# Schema.net
KiCad netlist of a schematic drawn in Altium Designer
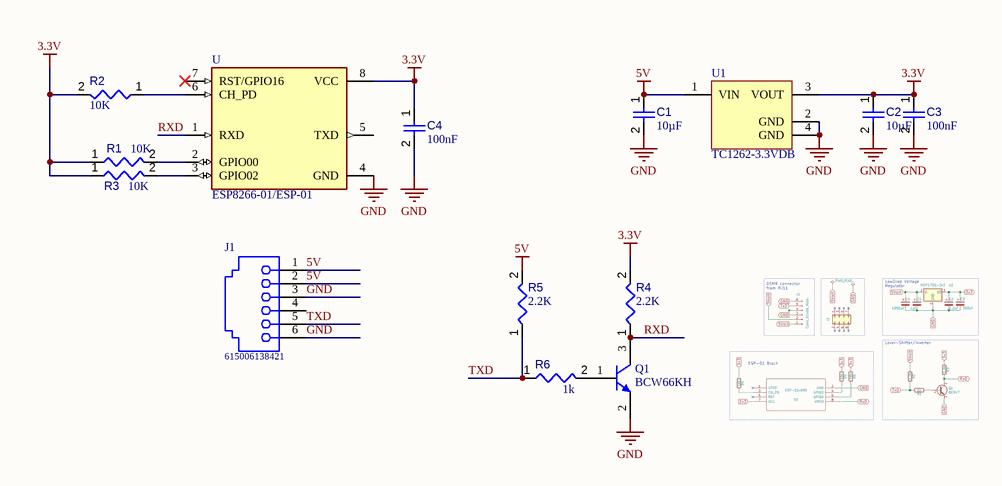
[diagram p0: Schema.SchDoc]

(export (version "E")
  (design (tool "Eeschema 10.0.6"))
  (components
    (comp (ref "C1")
      (value "10µF")
      (footprint "CAPC0805(2012)145_L")
      (description "Chip Capacitor, 10µF +/-20%, 25V, 0805, Thickness 1.45 mm")
      (fields (field (name "TOLERANCE") "10%") (field (name "Comment") "Capacitor 10µF +/-20% 25V 0805"))
      (libsource (lib "Merced College") (part "CAP-NP-2"))
    )
    (comp (ref "C2")
      (value "10µF")
      (footprint "CAPC0805(2012)145_L")
      (description "Chip Capacitor, 10µF +/-20%, 25V, 0805, Thickness 1.45 mm")
      (fields (field (name "TOLERANCE") "10%") (field (name "Comment") "Capacitor 10µF +/-20% 25V 0805"))
      (libsource (lib "Merced College") (part "CAP-NP-2"))
    )
    (comp (ref "C3")
      (value "100nF")
      (footprint "CAPC1608X90X40NL10T20")
      (description "Chip Capacitor, 100 nF, +/- 10%, 50 V, 0603 (1608 Metric)")
      (fields (field (name "TOLERANCE") "10%") (field (name "Comment") "Capacitor 100 nF +/-10% 50 V 0603"))
      (libsource (lib "Merced College") (part "CAP-NP-2"))
    )
    (comp (ref "C4")
      (value "100nF")
      (footprint "CAPC1608X90X40NL10T20")
      (description "Chip Capacitor, 100 nF, +/- 10%, 50 V, 0603 (1608 Metric)")
      (fields (field (name "TOLERANCE") "10%") (field (name "Comment") "Capacitor 100 nF +/-10% 50 V 0603"))
      (libsource (lib "Merced College") (part "CAP-NP-2"))
    )
    (comp (ref "J1")
      (value "615006138421")
      (footprint "615006138421")
      (description "Modular Jack WR-MJ, Tab Up, Plastic, Horizontal Entry, THT, 6P6C")
      (fields (field (name "MANUFACTURER") "Wurth Elektronik") (field (name "PUBLISHER") "WurthElektronik"))
      (libsource (lib "Altium Content Vault") (part "WE-CN-1P-F-J6"))
    )
    (comp (ref "Q1")
      (value "BCW66KH")
      (footprint "INF-SOT23_L")
      (description "NPN Silicon AF Transistor, 45 V VCEO, 800 mA IC, SOT23, Reel, Green")
      (fields (field (name "MANUFACTURER") "Infineon"))
      (libsource (lib "Altium Content Vault") (part "INF-BJTNPN-BEC-3"))
    )
    (comp (ref "R1")
      (value "10K")
      (footprint "RESC1608X55X25ML10T15")
      (description "Chip Resistor, 100 KOhm, +/- 1%, 0.1 W, -55 to 155 degC, 0603 (1608 Metric)")
      (fields (field (name "POWER") "100mW") (field (name "TOLERANCE") "1%"))
      (libsource (lib "Merced College") (part "RES-2"))
    )
    (comp (ref "R2")
      (value "10K")
      (footprint "RESC1608X55X25ML10T15")
      (description "Chip Resistor, 100 KOhm, +/- 1%, 0.1 W, -55 to 155 degC, 0603 (1608 Metric)")
      (fields (field (name "POWER") "100mW") (field (name "TOLERANCE") "1%"))
      (libsource (lib "Merced College") (part "RES-2"))
    )
    (comp (ref "R3")
      (value "10K")
      (footprint "RESC1608X55X25ML10T15")
      (description "Chip Resistor, 100 KOhm, +/- 1%, 0.1 W, -55 to 155 degC, 0603 (1608 Metric)")
      (fields (field (name "POWER") "100mW") (field (name "TOLERANCE") "1%"))
      (libsource (lib "Merced College") (part "RES-2"))
    )
    (comp (ref "R4")
      (value "2.2K")
      (footprint "RESC1608X55X25ML10T15")
      (description "Chip Resistor, 100 KOhm, +/- 1%, 0.1 W, -55 to 155 degC, 0603 (1608 Metric)")
      (fields (field (name "POWER") "100mW") (field (name "TOLERANCE") "1%"))
      (libsource (lib "Merced College") (part "RES-2"))
    )
    (comp (ref "R5")
      (value "2.2K")
      (footprint "RESC1608X55X25ML10T15")
      (description "Chip Resistor, 100 KOhm, +/- 1%, 0.1 W, -55 to 155 degC, 0603 (1608 Metric)")
      (fields (field (name "POWER") "100mW") (field (name "TOLERANCE") "1%"))
      (libsource (lib "Merced College") (part "RES-2"))
    )
    (comp (ref "R6")
      (value "1k")
      (footprint "RESC1608X55X25ML10T15")
      (description "Chip Resistor, 100 KOhm, +/- 1%, 0.1 W, -55 to 155 degC, 0603 (1608 Metric)")
      (fields (field (name "POWER") "100mW") (field (name "TOLERANCE") "1%"))
      (libsource (lib "Merced College") (part "RES-2"))
    )
    (comp (ref "U")
      (value "ESP8266-01/ESP-01")
      (footprint "XCVR_ESP8266-01/ESP-01")
      (description "ESP-01 wifi module")
      (fields (field (name "MF") "AI-Thinker"))
      (libsource (lib "ESP8266-01_ESP-01") (part "ESP8266-01/ESP-01"))
    )
    (comp (ref "U1")
      (value "TC1262-3.3VDB")
      (footprint "SOT-223-DB3_L")
      (description "500mA Fixed Output CMOS LDO, 3-Pin SOT-223, Extended Temperature")
      (libsource (lib "Altium Content Vault") (part "PM-LINEREG-TC1262-IL4"))
    )
  )
  (nets
    (net (code "2") (name "/RXD") (class "Default")
      (node (ref "Q1") (pin "3") (pinfunction "C_3") (pintype "passive"))
      (node (ref "R4") (pin "1") (pinfunction "1_1") (pintype "passive"))
      (node (ref "U") (pin "1") (pinfunction "RXD_1") (pintype "input"))
    )
    (net (code "3") (name "/TXD") (class "Default")
      (node (ref "J1") (pin "5") (pinfunction "5_5") (pintype "passive"))
      (node (ref "R5") (pin "1") (pinfunction "1_1") (pintype "passive"))
      (node (ref "R6") (pin "1") (pinfunction "1_1") (pintype "passive"))
    )
    (net (code "4") (name "3.3V") (class "Default")
      (node (ref "C2") (pin "1") (pinfunction "1_1") (pintype "passive"))
      (node (ref "C3") (pin "1") (pinfunction "1_1") (pintype "passive"))
      (node (ref "C4") (pin "1") (pinfunction "1_1") (pintype "passive"))
      (node (ref "R1") (pin "1") (pinfunction "1_1") (pintype "passive"))
      (node (ref "R2") (pin "2") (pinfunction "2_2") (pintype "passive"))
      (node (ref "R3") (pin "1") (pinfunction "1_1") (pintype "passive"))
      (node (ref "R4") (pin "2") (pinfunction "2_2") (pintype "passive"))
      (node (ref "U") (pin "8") (pinfunction "VCC_8") (pintype "power_in"))
      (node (ref "U1") (pin "3") (pinfunction "VOUT_3") (pintype "power_in"))
    )
    (net (code "5") (name "5V") (class "Default")
      (node (ref "C1") (pin "1") (pinfunction "1_1") (pintype "passive"))
      (node (ref "J1") (pin "1") (pinfunction "1_1") (pintype "passive"))
      (node (ref "J1") (pin "2") (pinfunction "2_2") (pintype "passive"))
      (node (ref "R5") (pin "2") (pinfunction "2_2") (pintype "passive"))
      (node (ref "U1") (pin "1") (pinfunction "VIN_1") (pintype "power_in"))
    )
    (net (code "6") (name "GND") (class "Default")
      (node (ref "C1") (pin "2") (pinfunction "2_2") (pintype "passive"))
      (node (ref "C2") (pin "2") (pinfunction "2_2") (pintype "passive"))
      (node (ref "C3") (pin "2") (pinfunction "2_2") (pintype "passive"))
      (node (ref "C4") (pin "2") (pinfunction "2_2") (pintype "passive"))
      (node (ref "J1") (pin "3") (pinfunction "3_3") (pintype "passive"))
      (node (ref "J1") (pin "6") (pinfunction "6_6") (pintype "passive"))
      (node (ref "Q1") (pin "2") (pinfunction "E_2") (pintype "passive"))
      (node (ref "U") (pin "4") (pinfunction "GND_4") (pintype "power_in"))
      (node (ref "U1") (pin "2") (pinfunction "GND_2") (pintype "power_in"))
      (node (ref "U1") (pin "4") (pinfunction "GND_4") (pintype "power_in"))
    )
    (net (code "7") (name "Net-(Q1-B)") (class "Default")
      (node (ref "Q1") (pin "1") (pinfunction "B_1") (pintype "passive"))
      (node (ref "R6") (pin "2") (pinfunction "2_2") (pintype "passive"))
    )
    (net (code "8") (name "Net-(U-CH_PD)") (class "Default")
      (node (ref "R2") (pin "1") (pinfunction "1_1") (pintype "passive"))
      (node (ref "U") (pin "6") (pinfunction "CH_PD_6") (pintype "input"))
    )
    (net (code "9") (name "Net-(U-GPIO00)") (class "Default")
      (node (ref "R1") (pin "2") (pinfunction "2_2") (pintype "passive"))
      (node (ref "U") (pin "2") (pinfunction "GPIO00_2") (pintype "bidirectional"))
    )
    (net (code "10") (name "Net-(U-GPIO02)") (class "Default")
      (node (ref "R3") (pin "2") (pinfunction "2_2") (pintype "passive"))
      (node (ref "U") (pin "3") (pinfunction "GPIO02_3") (pintype "bidirectional"))
    )
    (net (code "11") (name "unconnected-(J1-Pad4)") (class "Default")
      (node (ref "J1") (pin "4") (pinfunction "4_4") (pintype "passive"))
    )
    (net (code "12") (name "unconnected-(U-RST{slash}GPIO16-Pad7)") (class "Default")
      (node (ref "U") (pin "7") (pinfunction "RST/GPIO16_7") (pintype "input+no_connect"))
    )
    (net (code "13") (name "unconnected-(U-TXD-Pad5)") (class "Default")
      (node (ref "U") (pin "5") (pinfunction "TXD_5") (pintype "output"))
    )
  )
)
